# Morpheus_IMU.net
KiCad netlist of a schematic drawn in Altium Designer
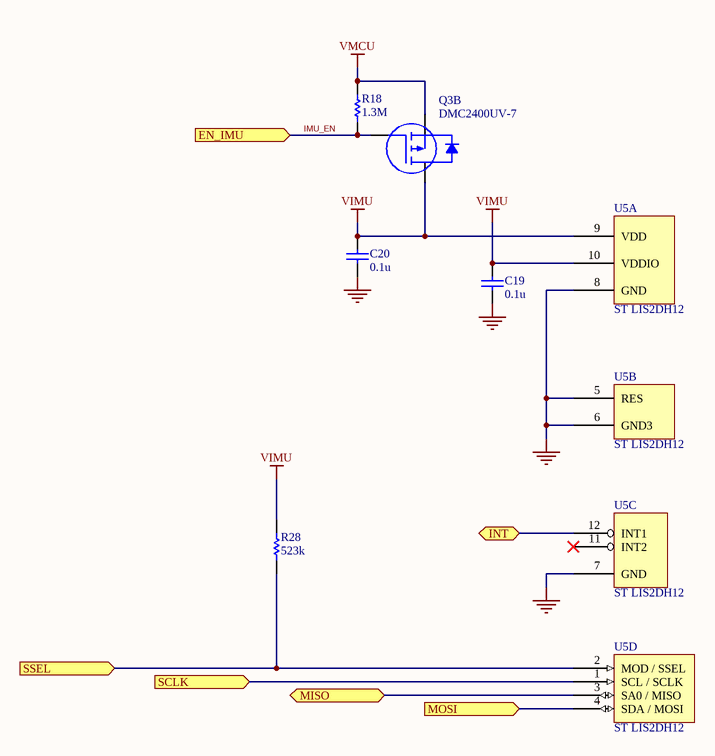
[diagram p0: Morpheus_IMU.SchDoc]

(export (version "E")
  (design (tool "Eeschema 10.0.6"))
  (components
    (comp (ref "C19")
      (value "0.1u")
      (footprint "CAP0402_SENSE_DVT")
      (description "Chip capacitor")
      (fields (field (name "TOLERANCE") "10%") (field (name "VOLTAGE") "50V"))
      (libsource (lib "Hello") (part "C_0.1u_10_50_X7R_0402"))
    )
    (comp (ref "C20")
      (value "0.1u")
      (footprint "CAP0402_SENSE_DVT")
      (description "Chip capacitor")
      (fields (field (name "TOLERANCE") "10%") (field (name "VOLTAGE") "50V"))
      (libsource (lib "Hello") (part "C_0.1u_10_50_X7R_0402"))
    )
    (comp (ref "Q3")
      (value "DMC2400UV-7")
      (footprint "SOT-563")
      (description "Dual PN-Channel MOSFET 1.2v drive 20V 0.88A")
      (libsource (lib "Smith_bot") (part "DMC2400UV-7"))
    )
    (comp (ref "R18")
      (value "1.3M")
      (footprint "RES0402_SENSE_DVT")
      (description "Chip Resistor")
      (fields (field (name "TOLERANCE") "5 %") (field (name "POWER") "0.1 W"))
      (libsource (lib "Hello") (part "R_1.3M_5_0.1_0402"))
    )
    (comp (ref "R28")
      (value "523k")
      (footprint "RES0402_SENSE_DVT")
      (description "Chip Resistor")
      (fields (field (name "TOLERANCE") "1 %") (field (name "POWER") "0.1 W"))
      (libsource (lib "Hello") (part "R_523k_1_0.1_0402"))
    )
    (comp (ref "U5")
      (value "ST LIS2DH12")
      (footprint "DFN50P200X200X80-12N")
      (description "STU Accelerometer")
      (libsource (lib "Smith_bot") (part "LIS2DH12"))
    )
  )
  (nets
    (net (code "1") (name "/IMU_EN") (class "Default")
      (node (ref "Q3") (pin "5") (pinfunction "G2_5") (pintype "passive"))
      (node (ref "R18") (pin "1") (pinfunction "1_1") (pintype "passive"))
    )
    (net (code "2") (name "/INT") (class "Default")
      (node (ref "U5") (pin "12") (pinfunction "INT1_12") (pintype "open_emitter"))
    )
    (net (code "3") (name "/MISO") (class "Default")
      (node (ref "U5") (pin "3") (pinfunction "SA0_/_MISO_3") (pintype "bidirectional"))
    )
    (net (code "4") (name "/MOSI") (class "Default")
      (node (ref "U5") (pin "4") (pinfunction "SDA_/_MOSI_4") (pintype "bidirectional"))
    )
    (net (code "5") (name "/SCLK") (class "Default")
      (node (ref "U5") (pin "1") (pinfunction "SCL_/_SCLK_1") (pintype "input"))
    )
    (net (code "6") (name "/SSEL") (class "Default")
      (node (ref "R28") (pin "1") (pinfunction "1_1") (pintype "passive"))
      (node (ref "U5") (pin "2") (pinfunction "MOD_/_SSEL_2") (pintype "input"))
    )
    (net (code "7") (name "GND") (class "Default")
      (node (ref "C19") (pin "1") (pinfunction "1_1") (pintype "passive"))
      (node (ref "C20") (pin "1") (pinfunction "1_1") (pintype "passive"))
      (node (ref "U5") (pin "5") (pinfunction "RES_5") (pintype "passive"))
      (node (ref "U5") (pin "6") (pinfunction "GND3_6") (pintype "power_in"))
      (node (ref "U5") (pin "7") (pinfunction "GND_7") (pintype "power_in"))
      (node (ref "U5") (pin "8") (pinfunction "GND_8") (pintype "power_in"))
    )
    (net (code "8") (name "VIMU") (class "Default")
      (node (ref "C19") (pin "2") (pinfunction "2_2") (pintype "passive"))
      (node (ref "C20") (pin "2") (pinfunction "2_2") (pintype "passive"))
      (node (ref "Q3") (pin "3") (pinfunction "D2_3") (pintype "passive"))
      (node (ref "R28") (pin "2") (pinfunction "2_2") (pintype "passive"))
      (node (ref "U5") (pin "10") (pinfunction "VDDIO_10") (pintype "power_in"))
      (node (ref "U5") (pin "9") (pinfunction "VDD_9") (pintype "power_in"))
    )
    (net (code "9") (name "VMCU") (class "Default")
      (node (ref "Q3") (pin "4") (pinfunction "S2_4") (pintype "passive"))
      (node (ref "R18") (pin "2") (pinfunction "2_2") (pintype "passive"))
    )
    (net (code "10") (name "unconnected-(U5C-INT2-Pad11)") (class "Default")
      (node (ref "U5") (pin "11") (pinfunction "INT2_11") (pintype "open_collector+no_connect"))
    )
  )
)
